# Wilssen_core_v0_201a.net
KiCad netlist of a schematic drawn in EAGLE
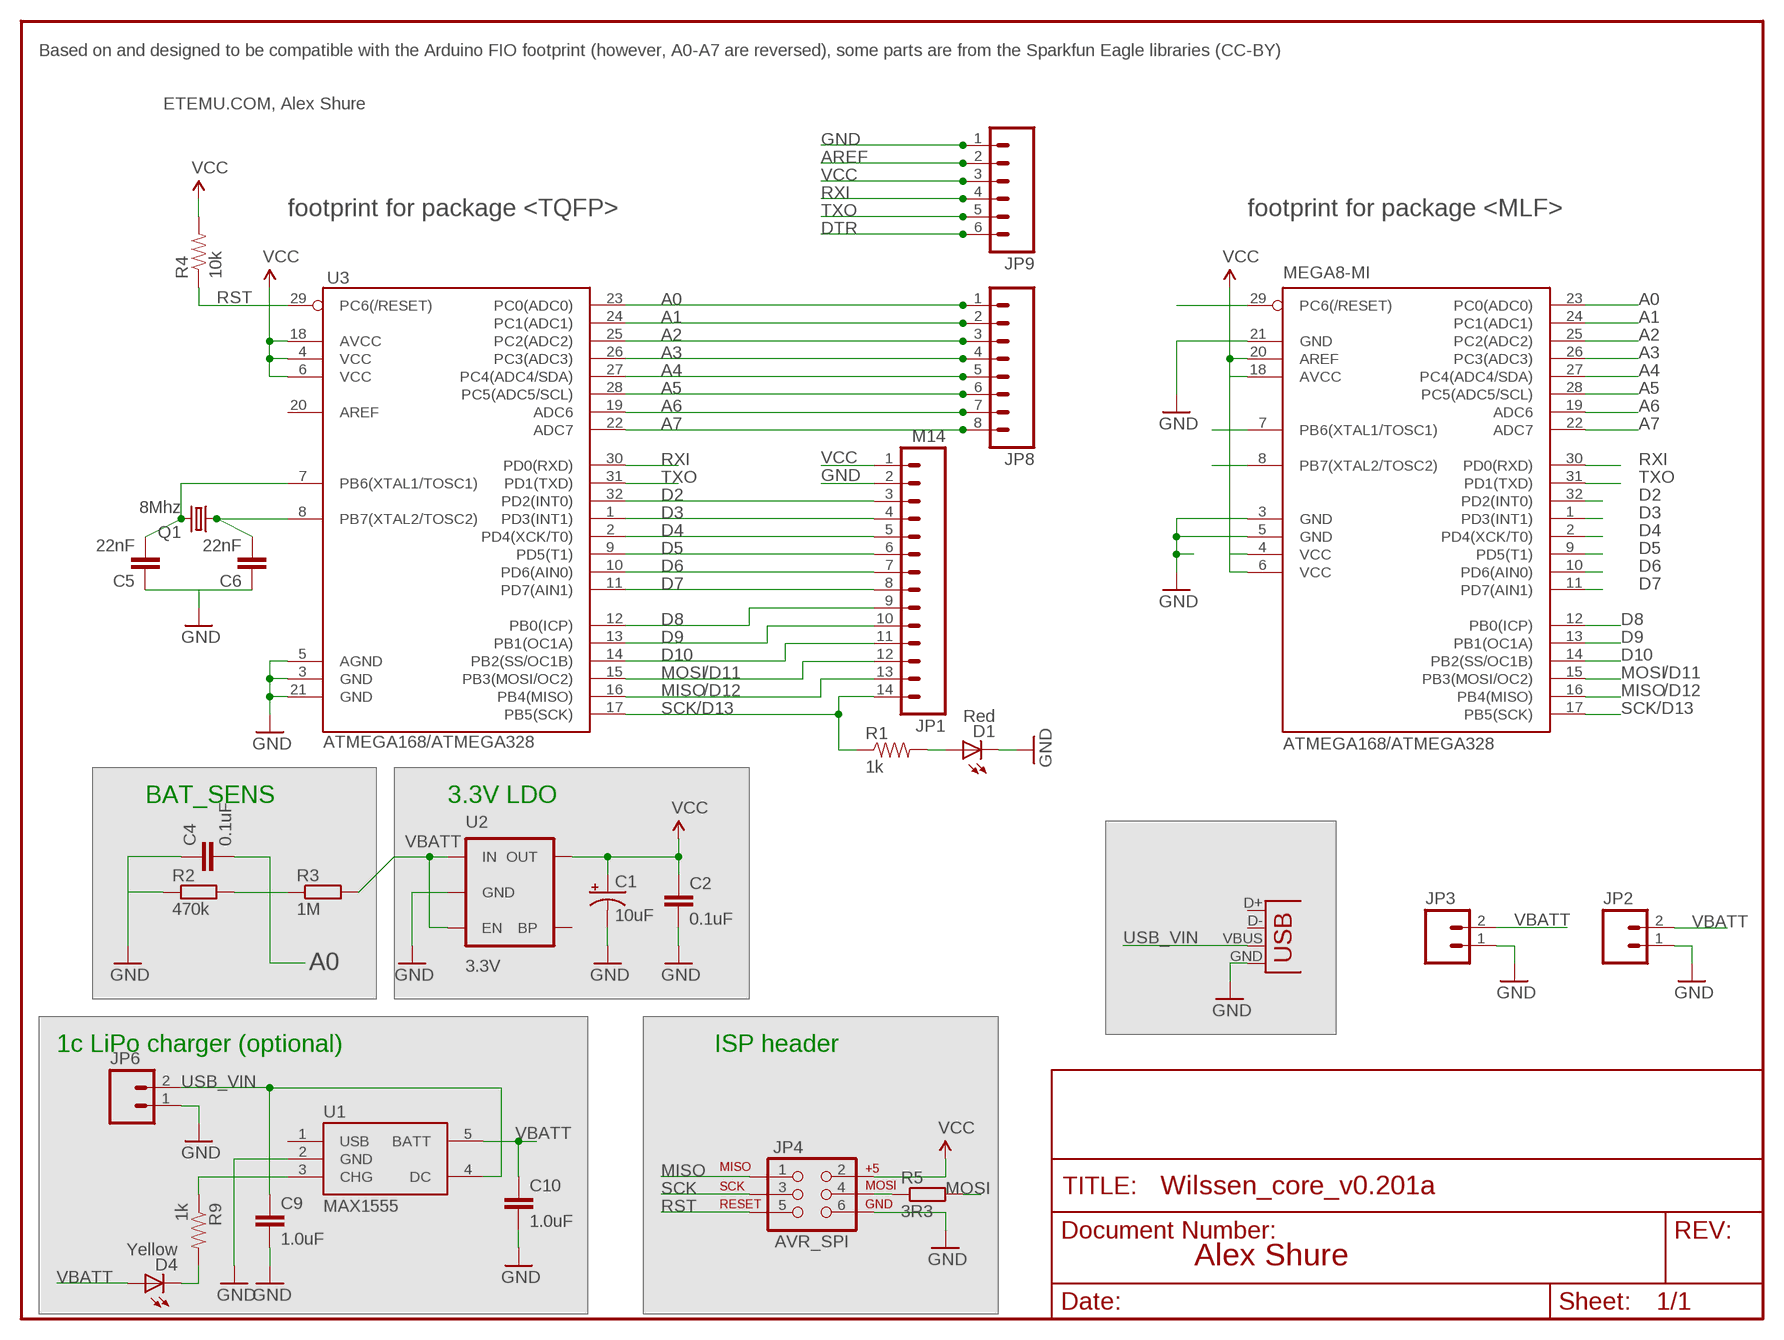
[diagram p0: schematic, sheet 1]

(export (version "E")
  (design (tool "Eeschema 10.0.6"))
  (components
    (comp (ref "ATMEGA168/ATMEGA328")
      (value "MEGA8-MI")
      (footprint "eagle-import:MLF32")
      (fields (field (name "MPN") "ATMEGA88PA-MU"))
      (libsource (lib "eagle-import") (part "MEGA8-MI"))
    )
    (comp (ref "C1")
      (value "10uF")
      (footprint "eagle-import:EIA3216")
      (libsource (lib "eagle-import") (part "CAP_POL1206"))
    )
    (comp (ref "C2")
      (value "0.1uF")
      (footprint "eagle-import:0805")
      (libsource (lib "eagle-import") (part "CAP0805"))
    )
    (comp (ref "C4")
      (value "0.1uF")
      (footprint "eagle-import:0805")
      (libsource (lib "eagle-import") (part "CAP0805"))
    )
    (comp (ref "C5")
      (value "22nF")
      (footprint "eagle-import:0805")
      (libsource (lib "eagle-import") (part "CAP0805"))
    )
    (comp (ref "C6")
      (value "22nF")
      (footprint "eagle-import:0805")
      (libsource (lib "eagle-import") (part "CAP0805"))
    )
    (comp (ref "C9")
      (value "1.0uF")
      (footprint "eagle-import:0402-CAP")
      (libsource (lib "eagle-import") (part "CAP0402-CAP"))
    )
    (comp (ref "C10")
      (value "1.0uF")
      (footprint "eagle-import:0402-CAP")
      (libsource (lib "eagle-import") (part "CAP0402-CAP"))
    )
    (comp (ref "D1")
      (value "Red")
      (footprint "eagle-import:LED-0603")
      (libsource (lib "eagle-import") (part "LED0603"))
    )
    (comp (ref "D4")
      (value "Yellow")
      (footprint "eagle-import:LED-0603")
      (libsource (lib "eagle-import") (part "LED0603"))
    )
    (comp (ref "JP1")
      (value "M14")
      (footprint "eagle-import:1X14")
      (libsource (lib "eagle-import") (part "M14"))
    )
    (comp (ref "JP2")
      (value "M02PTH")
      (footprint "eagle-import:1X02")
      (libsource (lib "eagle-import") (part "M02PTH"))
    )
    (comp (ref "JP3")
      (value "M02-JST-2MM-SMT")
      (footprint "eagle-import:S2B-PH")
      (libsource (lib "eagle-import") (part "M02-JST-2MM-SMT"))
    )
    (comp (ref "JP4")
      (value "AVR_SPI")
      (footprint "eagle-import:2X3")
      (libsource (lib "eagle-import") (part "AVR_SPI_PRG_6PTH"))
    )
    (comp (ref "JP6")
      (value "M02PTH")
      (footprint "eagle-import:1X02")
      (libsource (lib "eagle-import") (part "M02PTH"))
    )
    (comp (ref "JP8")
      (value "M081X08")
      (footprint "eagle-import:1X08")
      (libsource (lib "eagle-import") (part "M081X08"))
    )
    (comp (ref "JP9")
      (value "M06SIP")
      (footprint "eagle-import:1X06")
      (libsource (lib "eagle-import") (part "M06SIP"))
    )
    (comp (ref "Q1")
      (value "8Mhz")
      (footprint "eagle-import:SM49")
      (libsource (lib "eagle-import") (part "CRYSTALSM49"))
    )
    (comp (ref "R1")
      (value "1k")
      (footprint "eagle-import:0805")
      (libsource (lib "eagle-import") (part "RESISTOR"))
    )
    (comp (ref "R2")
      (value "470k")
      (footprint "eagle-import:R0805")
      (libsource (lib "eagle-import") (part "R-EU_R0805"))
    )
    (comp (ref "R3")
      (value "1M")
      (footprint "eagle-import:R0805")
      (libsource (lib "eagle-import") (part "R-EU_R0805"))
    )
    (comp (ref "R4")
      (value "10k")
      (footprint "eagle-import:1206")
      (libsource (lib "eagle-import") (part "RESISTOR1206"))
    )
    (comp (ref "R5")
      (value "3R3")
      (footprint "eagle-import:R1206")
      (libsource (lib "eagle-import") (part "R-EU_R1206"))
    )
    (comp (ref "R9")
      (value "1k")
      (footprint "eagle-import:0402-RES")
      (libsource (lib "eagle-import") (part "RESISTOR0402-RES"))
    )
    (comp (ref "U1")
      (value "MAX1555")
      (footprint "eagle-import:SOT23-5")
      (libsource (lib "eagle-import") (part "MAX1555"))
    )
    (comp (ref "U2")
      (value "3.3V")
      (footprint "eagle-import:SOT23-5")
      (libsource (lib "eagle-import") (part "V_REG_LDOSMD"))
    )
    (comp (ref "U3")
      (value "ATMEGA168/ATMEGA328")
      (footprint "eagle-import:TQFP32-08")
      (libsource (lib "eagle-import") (part "ATMEGA168"))
    )
    (comp (ref "X1")
      (value "USBSMD")
      (footprint "eagle-import:USB-MINIB")
      (libsource (lib "eagle-import") (part "USBSMD"))
    )
  )
  (nets
    (net (code "1") (name "/A0") (class "Default")
      (node (ref "ATMEGA168/ATMEGA328") (pin "23") (pinfunction "PC0(ADC0)_23") (pintype "bidirectional"))
      (node (ref "C4") (pin "2") (pinfunction "2_2") (pintype "passive"))
      (node (ref "JP8") (pin "1") (pinfunction "1_1") (pintype "passive"))
      (node (ref "R2") (pin "2") (pinfunction "2_2") (pintype "passive"))
      (node (ref "R3") (pin "1") (pinfunction "1_1") (pintype "passive"))
      (node (ref "U3") (pin "23") (pinfunction "PC0(ADC0)_23") (pintype "bidirectional"))
    )
    (net (code "2") (name "/A1") (class "Default")
      (node (ref "ATMEGA168/ATMEGA328") (pin "24") (pinfunction "PC1(ADC1)_24") (pintype "bidirectional"))
      (node (ref "JP8") (pin "2") (pinfunction "2_2") (pintype "passive"))
      (node (ref "U3") (pin "24") (pinfunction "PC1(ADC1)_24") (pintype "bidirectional"))
    )
    (net (code "3") (name "/A2") (class "Default")
      (node (ref "ATMEGA168/ATMEGA328") (pin "25") (pinfunction "PC2(ADC2)_25") (pintype "bidirectional"))
      (node (ref "JP8") (pin "3") (pinfunction "3_3") (pintype "passive"))
      (node (ref "U3") (pin "25") (pinfunction "PC2(ADC2)_25") (pintype "bidirectional"))
    )
    (net (code "4") (name "/A3") (class "Default")
      (node (ref "ATMEGA168/ATMEGA328") (pin "26") (pinfunction "PC3(ADC3)_26") (pintype "bidirectional"))
      (node (ref "JP8") (pin "4") (pinfunction "4_4") (pintype "passive"))
      (node (ref "U3") (pin "26") (pinfunction "PC3(ADC3)_26") (pintype "bidirectional"))
    )
    (net (code "5") (name "/A4") (class "Default")
      (node (ref "ATMEGA168/ATMEGA328") (pin "27") (pinfunction "PC4(ADC4/SDA)_27") (pintype "bidirectional"))
      (node (ref "JP8") (pin "5") (pinfunction "5_5") (pintype "passive"))
      (node (ref "U3") (pin "27") (pinfunction "PC4(ADC4/SDA)_27") (pintype "bidirectional"))
    )
    (net (code "6") (name "/A5") (class "Default")
      (node (ref "ATMEGA168/ATMEGA328") (pin "28") (pinfunction "PC5(ADC5/SCL)_28") (pintype "bidirectional"))
      (node (ref "JP8") (pin "6") (pinfunction "6_6") (pintype "passive"))
      (node (ref "U3") (pin "28") (pinfunction "PC5(ADC5/SCL)_28") (pintype "bidirectional"))
    )
    (net (code "7") (name "/A6") (class "Default")
      (node (ref "ATMEGA168/ATMEGA328") (pin "19") (pinfunction "ADC6_19") (pintype "bidirectional"))
      (node (ref "JP8") (pin "7") (pinfunction "7_7") (pintype "passive"))
      (node (ref "U3") (pin "19") (pinfunction "ADC6_19") (pintype "bidirectional"))
    )
    (net (code "8") (name "/A7") (class "Default")
      (node (ref "ATMEGA168/ATMEGA328") (pin "22") (pinfunction "ADC7_22") (pintype "bidirectional"))
      (node (ref "JP8") (pin "8") (pinfunction "8_8") (pintype "passive"))
      (node (ref "U3") (pin "22") (pinfunction "ADC7_22") (pintype "bidirectional"))
    )
    (net (code "9") (name "/AREF") (class "Default")
      (node (ref "JP9") (pin "2") (pinfunction "2_2") (pintype "passive"))
    )
    (net (code "10") (name "/D2") (class "Default")
      (node (ref "ATMEGA168/ATMEGA328") (pin "32") (pinfunction "PD2(INT0)_32") (pintype "bidirectional"))
      (node (ref "JP1") (pin "3") (pinfunction "3_3") (pintype "passive"))
      (node (ref "U3") (pin "32") (pinfunction "PD2(INT0)_32") (pintype "bidirectional"))
    )
    (net (code "11") (name "/D3") (class "Default")
      (node (ref "ATMEGA168/ATMEGA328") (pin "1") (pinfunction "PD3(INT1)_1") (pintype "bidirectional"))
      (node (ref "JP1") (pin "4") (pinfunction "4_4") (pintype "passive"))
      (node (ref "U3") (pin "1") (pinfunction "PD3(INT1)_1") (pintype "bidirectional"))
    )
    (net (code "12") (name "/D4") (class "Default")
      (node (ref "ATMEGA168/ATMEGA328") (pin "2") (pinfunction "PD4(XCK/T0)_2") (pintype "bidirectional"))
      (node (ref "JP1") (pin "5") (pinfunction "5_5") (pintype "passive"))
      (node (ref "U3") (pin "2") (pinfunction "PD4(XCK/T0)_2") (pintype "bidirectional"))
    )
    (net (code "13") (name "/D5") (class "Default")
      (node (ref "ATMEGA168/ATMEGA328") (pin "9") (pinfunction "PD5(T1)_9") (pintype "bidirectional"))
      (node (ref "JP1") (pin "6") (pinfunction "6_6") (pintype "passive"))
      (node (ref "U3") (pin "9") (pinfunction "PD5(T1)_9") (pintype "bidirectional"))
    )
    (net (code "14") (name "/D6") (class "Default")
      (node (ref "ATMEGA168/ATMEGA328") (pin "10") (pinfunction "PD6(AIN0)_10") (pintype "bidirectional"))
      (node (ref "JP1") (pin "7") (pinfunction "7_7") (pintype "passive"))
      (node (ref "U3") (pin "10") (pinfunction "PD6(AIN0)_10") (pintype "bidirectional"))
    )
    (net (code "15") (name "/D7") (class "Default")
      (node (ref "ATMEGA168/ATMEGA328") (pin "11") (pinfunction "PD7(AIN1)_11") (pintype "bidirectional"))
      (node (ref "JP1") (pin "8") (pinfunction "8_8") (pintype "passive"))
      (node (ref "U3") (pin "11") (pinfunction "PD7(AIN1)_11") (pintype "bidirectional"))
    )
    (net (code "16") (name "/D8") (class "Default")
      (node (ref "ATMEGA168/ATMEGA328") (pin "12") (pinfunction "PB0(ICP)_12") (pintype "bidirectional"))
      (node (ref "JP1") (pin "9") (pinfunction "9_9") (pintype "passive"))
      (node (ref "U3") (pin "12") (pinfunction "PB0(ICP)_12") (pintype "bidirectional"))
    )
    (net (code "17") (name "/D9") (class "Default")
      (node (ref "ATMEGA168/ATMEGA328") (pin "13") (pinfunction "PB1(OC1A)_13") (pintype "bidirectional"))
      (node (ref "JP1") (pin "10") (pinfunction "10_10") (pintype "passive"))
      (node (ref "U3") (pin "13") (pinfunction "PB1(OC1A)_13") (pintype "bidirectional"))
    )
    (net (code "18") (name "/D10") (class "Default")
      (node (ref "ATMEGA168/ATMEGA328") (pin "14") (pinfunction "PB2(SS/OC1B)_14") (pintype "bidirectional"))
      (node (ref "JP1") (pin "11") (pinfunction "11_11") (pintype "passive"))
      (node (ref "U3") (pin "14") (pinfunction "PB2(SS/OC1B)_14") (pintype "bidirectional"))
    )
    (net (code "19") (name "/DTR") (class "Default")
      (node (ref "JP9") (pin "6") (pinfunction "6_6") (pintype "passive"))
    )
    (net (code "20") (name "/MISO") (class "Default")
      (node (ref "ATMEGA168/ATMEGA328") (pin "16") (pinfunction "PB4(MISO)_16") (pintype "bidirectional"))
      (node (ref "JP1") (pin "13") (pinfunction "13_13") (pintype "passive"))
      (node (ref "JP4") (pin "1") (pinfunction "1_1") (pintype "passive"))
      (node (ref "U3") (pin "16") (pinfunction "PB4(MISO)_16") (pintype "bidirectional"))
    )
    (net (code "21") (name "/MOSI") (class "Default")
      (node (ref "ATMEGA168/ATMEGA328") (pin "15") (pinfunction "PB3(MOSI/OC2)_15") (pintype "bidirectional"))
      (node (ref "JP1") (pin "12") (pinfunction "12_12") (pintype "passive"))
      (node (ref "R5") (pin "2") (pinfunction "2_2") (pintype "passive"))
      (node (ref "U3") (pin "15") (pinfunction "PB3(MOSI/OC2)_15") (pintype "bidirectional"))
    )
    (net (code "22") (name "/RST") (class "Default")
      (node (ref "JP4") (pin "5") (pinfunction "5_5") (pintype "passive"))
      (node (ref "R4") (pin "1") (pinfunction "1_1") (pintype "passive"))
      (node (ref "U3") (pin "29") (pinfunction "PC6(/RESET)_29") (pintype "bidirectional"))
    )
    (net (code "23") (name "/RXI") (class "Default")
      (node (ref "ATMEGA168/ATMEGA328") (pin "30") (pinfunction "PD0(RXD)_30") (pintype "bidirectional"))
      (node (ref "JP9") (pin "4") (pinfunction "4_4") (pintype "passive"))
      (node (ref "U3") (pin "30") (pinfunction "PD0(RXD)_30") (pintype "bidirectional"))
    )
    (net (code "24") (name "/SCK") (class "Default")
      (node (ref "ATMEGA168/ATMEGA328") (pin "17") (pinfunction "PB5(SCK)_17") (pintype "bidirectional"))
      (node (ref "JP1") (pin "14") (pinfunction "14_14") (pintype "passive"))
      (node (ref "JP4") (pin "3") (pinfunction "3_3") (pintype "passive"))
      (node (ref "R1") (pin "1") (pinfunction "1_1") (pintype "passive"))
      (node (ref "U3") (pin "17") (pinfunction "PB5(SCK)_17") (pintype "bidirectional"))
    )
    (net (code "25") (name "/TXO") (class "Default")
      (node (ref "ATMEGA168/ATMEGA328") (pin "31") (pinfunction "PD1(TXD)_31") (pintype "bidirectional"))
      (node (ref "JP9") (pin "5") (pinfunction "5_5") (pintype "passive"))
      (node (ref "U3") (pin "31") (pinfunction "PD1(TXD)_31") (pintype "bidirectional"))
    )
    (net (code "26") (name "/USB_VIN") (class "Default")
      (node (ref "C9") (pin "1") (pinfunction "1_1") (pintype "passive"))
      (node (ref "JP6") (pin "2") (pinfunction "2_2") (pintype "passive"))
      (node (ref "U1") (pin "4") (pinfunction "DC_4") (pintype "bidirectional"))
      (node (ref "X1") (pin "VBUS") (pinfunction "VBUS_VBUS") (pintype "bidirectional"))
    )
    (net (code "27") (name "/VBATT") (class "Default")
      (node (ref "C10") (pin "1") (pinfunction "1_1") (pintype "passive"))
      (node (ref "D4") (pin "A") (pinfunction "A_A") (pintype "passive"))
      (node (ref "JP2") (pin "2") (pinfunction "2_2") (pintype "passive"))
      (node (ref "JP3") (pin "2") (pinfunction "2_2") (pintype "passive"))
      (node (ref "R3") (pin "2") (pinfunction "2_2") (pintype "passive"))
      (node (ref "U1") (pin "5") (pinfunction "BATT_5") (pintype "bidirectional"))
      (node (ref "U2") (pin "1") (pinfunction "IN_1") (pintype "input"))
      (node (ref "U2") (pin "3") (pinfunction "EN_3") (pintype "input"))
    )
    (net (code "28") (name "/XTAL1") (class "Default")
      (node (ref "ATMEGA168/ATMEGA328") (pin "7") (pinfunction "PB6(XTAL1/TOSC1)_7") (pintype "bidirectional"))
      (node (ref "C5") (pin "2") (pinfunction "2_2") (pintype "passive"))
      (node (ref "Q1") (pin "2") (pinfunction "2_2") (pintype "passive"))
      (node (ref "U3") (pin "7") (pinfunction "PB6(XTAL1/TOSC1)_7") (pintype "bidirectional"))
    )
    (net (code "29") (name "/XTAL2") (class "Default")
      (node (ref "ATMEGA168/ATMEGA328") (pin "8") (pinfunction "PB7(XTAL2/TOSC2)_8") (pintype "bidirectional"))
      (node (ref "C6") (pin "2") (pinfunction "2_2") (pintype "passive"))
      (node (ref "Q1") (pin "1") (pinfunction "1_1") (pintype "passive"))
      (node (ref "U3") (pin "8") (pinfunction "PB7(XTAL2/TOSC2)_8") (pintype "bidirectional"))
    )
    (net (code "30") (name "GND") (class "Default")
      (node (ref "ATMEGA168/ATMEGA328") (pin "21") (pinfunction "GND_21") (pintype "power_in"))
      (node (ref "ATMEGA168/ATMEGA328") (pin "3") (pinfunction "GND_3") (pintype "power_in"))
      (node (ref "ATMEGA168/ATMEGA328") (pin "5") (pinfunction "GND_5") (pintype "power_in"))
      (node (ref "C1") (pin "C") (pinfunction "-_C") (pintype "passive"))
      (node (ref "C10") (pin "2") (pinfunction "2_2") (pintype "passive"))
      (node (ref "C2") (pin "2") (pinfunction "2_2") (pintype "passive"))
      (node (ref "C4") (pin "1") (pinfunction "1_1") (pintype "passive"))
      (node (ref "C5") (pin "1") (pinfunction "1_1") (pintype "passive"))
      (node (ref "C6") (pin "1") (pinfunction "1_1") (pintype "passive"))
      (node (ref "C9") (pin "2") (pinfunction "2_2") (pintype "passive"))
      (node (ref "D1") (pin "C") (pinfunction "C_C") (pintype "passive"))
      (node (ref "JP1") (pin "2") (pinfunction "2_2") (pintype "passive"))
      (node (ref "JP2") (pin "1") (pinfunction "1_1") (pintype "passive"))
      (node (ref "JP3") (pin "1") (pinfunction "1_1") (pintype "passive"))
      (node (ref "JP4") (pin "6") (pinfunction "6_6") (pintype "passive"))
      (node (ref "JP6") (pin "1") (pinfunction "1_1") (pintype "passive"))
      (node (ref "JP9") (pin "1") (pinfunction "1_1") (pintype "passive"))
      (node (ref "R2") (pin "1") (pinfunction "1_1") (pintype "passive"))
      (node (ref "U1") (pin "2") (pinfunction "GND_2") (pintype "bidirectional"))
      (node (ref "U2") (pin "2") (pinfunction "GND_2") (pintype "input"))
      (node (ref "U3") (pin "21") (pinfunction "GND_21") (pintype "bidirectional"))
      (node (ref "U3") (pin "3") (pinfunction "GND_3") (pintype "bidirectional"))
      (node (ref "U3") (pin "5") (pinfunction "AGND_5") (pintype "bidirectional"))
      (node (ref "X1") (pin "GND") (pinfunction "GND_GND") (pintype "bidirectional"))
    )
    (net (code "31") (name "Net-(D1-PadA)") (class "Default")
      (node (ref "D1") (pin "A") (pinfunction "A_A") (pintype "passive"))
      (node (ref "R1") (pin "2") (pinfunction "2_2") (pintype "passive"))
    )
    (net (code "32") (name "Net-(D4-PadC)") (class "Default")
      (node (ref "D4") (pin "C") (pinfunction "C_C") (pintype "passive"))
      (node (ref "R9") (pin "2") (pinfunction "2_2") (pintype "passive"))
    )
    (net (code "33") (name "Net-(JP4-Pad4)") (class "Default")
      (node (ref "JP4") (pin "4") (pinfunction "4_4") (pintype "passive"))
      (node (ref "R5") (pin "1") (pinfunction "1_1") (pintype "passive"))
    )
    (net (code "34") (name "Net-(U1-CHG)") (class "Default")
      (node (ref "R9") (pin "1") (pinfunction "1_1") (pintype "passive"))
      (node (ref "U1") (pin "3") (pinfunction "CHG_3") (pintype "bidirectional"))
    )
    (net (code "35") (name "VCC") (class "Default")
      (node (ref "ATMEGA168/ATMEGA328") (pin "18") (pinfunction "AVCC_18") (pintype "power_in"))
      (node (ref "ATMEGA168/ATMEGA328") (pin "20") (pinfunction "AREF_20") (pintype "passive"))
      (node (ref "ATMEGA168/ATMEGA328") (pin "4") (pinfunction "VCC_4") (pintype "power_in"))
      (node (ref "ATMEGA168/ATMEGA328") (pin "6") (pinfunction "VCC_6") (pintype "power_in"))
      (node (ref "C1") (pin "A") (pinfunction "+_A") (pintype "passive"))
      (node (ref "C2") (pin "1") (pinfunction "1_1") (pintype "passive"))
      (node (ref "JP1") (pin "1") (pinfunction "1_1") (pintype "passive"))
      (node (ref "JP4") (pin "2") (pinfunction "2_2") (pintype "passive"))
      (node (ref "JP9") (pin "3") (pinfunction "3_3") (pintype "passive"))
      (node (ref "R4") (pin "2") (pinfunction "2_2") (pintype "passive"))
      (node (ref "U2") (pin "5") (pinfunction "OUT_5") (pintype "passive"))
      (node (ref "U3") (pin "18") (pinfunction "AVCC_18") (pintype "bidirectional"))
      (node (ref "U3") (pin "4") (pinfunction "VCC_4") (pintype "bidirectional"))
      (node (ref "U3") (pin "6") (pinfunction "VCC_6") (pintype "bidirectional"))
    )
    (net (code "36") (name "unconnected-(ATMEGA168/ATMEGA328-PC6({slash}RESET)-Pad29)") (class "Default")
      (node (ref "ATMEGA168/ATMEGA328") (pin "29") (pinfunction "PC6(/RESET)_29") (pintype "bidirectional"))
    )
    (net (code "37") (name "unconnected-(U1-USB-Pad1)") (class "Default")
      (node (ref "U1") (pin "1") (pinfunction "USB_1") (pintype "bidirectional"))
    )
    (net (code "38") (name "unconnected-(U2-BP-Pad4)") (class "Default")
      (node (ref "U2") (pin "4") (pinfunction "BP_4") (pintype "input"))
    )
    (net (code "39") (name "unconnected-(U3-AREF-Pad20)") (class "Default")
      (node (ref "U3") (pin "20") (pinfunction "AREF_20") (pintype "bidirectional"))
    )
    (net (code "40") (name "unconnected-(X1-PadD+)") (class "Default")
      (node (ref "X1") (pin "D+") (pinfunction "D+_D+") (pintype "bidirectional"))
    )
    (net (code "41") (name "unconnected-(X1-PadD-)") (class "Default")
      (node (ref "X1") (pin "D-") (pinfunction "D-_D-") (pintype "bidirectional"))
    )
  )
)
